# Motor_Controllers.net
KiCad netlist of a schematic drawn in Altium Designer
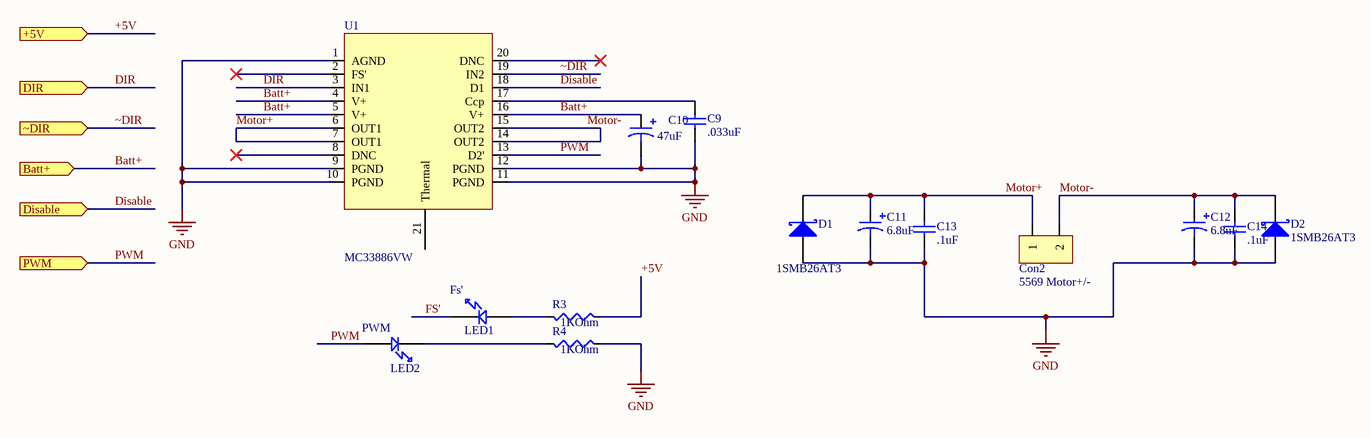
[diagram p0: Motor Controllers.SchDoc]

(export (version "E")
  (design (tool "Eeschema 10.0.6"))
  (components
    (comp (ref "C9")
      (value ".033uF")
      (footprint "PassiveComponents:0805 (2012) Capacitor")
      (description "Capacitor")
      (libsource (lib "PassiveComponents") (part "Capacitor (non-polarized)"))
    )
    (comp (ref "C10")
      (value "47uF")
      (footprint "PassiveComponents:Radial_6.3mmDia_SM_D")
      (description "Capacitor (polarized)")
      (libsource (lib "PassiveComponents") (part "Capacitor (polarized)"))
    )
    (comp (ref "C11")
      (value "6.8uF")
      (footprint "PassiveComponents:Radial_8mmDia_SM_E")
      (description "Capacitor (polarized)")
      (libsource (lib "PassiveComponents") (part "Capacitor (polarized)"))
    )
    (comp (ref "C12")
      (value "6.8uF")
      (footprint "PassiveComponents:Radial_8mmDia_SM_E")
      (description "Capacitor (polarized)")
      (libsource (lib "PassiveComponents") (part "Capacitor (polarized)"))
    )
    (comp (ref "C13")
      (value ".1uF")
      (footprint "PassiveComponents:0805 (2012) Capacitor")
      (description "Capacitor")
      (libsource (lib "PassiveComponents") (part "Capacitor (non-polarized)"))
    )
    (comp (ref "C14")
      (value ".1uF")
      (footprint "PassiveComponents:0805 (2012) Capacitor")
      (description "Capacitor")
      (libsource (lib "PassiveComponents") (part "Capacitor (non-polarized)"))
    )
    (comp (ref "Con2")
      (value "5569 Motor+/-")
      (footprint "Molex:5569 Mini-Fit Jr 2-Pos Right Angle w/ PCB Mounting Flange")
      (libsource (lib "Molex") (part "5569 Mini-Fit Jr 2-Pos Right Angle"))
    )
    (comp (ref "D1")
      (value "1SMB26AT3")
      (footprint "SMB")
      (description "Schottky Diode")
      (fields (field (name "PUBLISHER") "Altium Limited"))
      (libsource (lib "Miscellaneous Devices") (part "D Schottky"))
    )
    (comp (ref "D2")
      (value "1SMB26AT3")
      (footprint "SMB")
      (description "Schottky Diode")
      (fields (field (name "PUBLISHER") "Altium Limited"))
      (libsource (lib "Miscellaneous Devices") (part "D Schottky"))
    )
    (comp (ref "LED1")
      (value "Fs'")
      (footprint "LEDs:LED 0805")
      (description "Standard LED")
      (libsource (lib "PassiveComponents") (part "LED"))
    )
    (comp (ref "LED2")
      (value "PWM")
      (footprint "LEDs:LED 0805")
      (description "Standard LED")
      (libsource (lib "PassiveComponents") (part "LED"))
    )
    (comp (ref "R3")
      (value "1KOhm")
      (footprint "PassiveComponents:R 0805 (2012) RESISTOR")
      (description "Resistor")
      (libsource (lib "PassiveComponents") (part "Resistor"))
    )
    (comp (ref "R4")
      (value "1KOhm")
      (footprint "PassiveComponents:R 0805 (2012) RESISTOR")
      (description "Resistor")
      (libsource (lib "PassiveComponents") (part "Resistor"))
    )
    (comp (ref "U1")
      (value "MC33886VW")
      (footprint "SOP127P1420X340_HS-20N")
      (description "Motor Controller")
      (libsource (lib "MC33886VW") (part "MC33886VW"))
    )
  )
  (nets
    (net (code "1") (name "/+5V") (class "Default")
      (node (ref "R3") (pin "2") (pinfunction "2_2") (pintype "passive"))
    )
    (net (code "2") (name "/Batt+") (class "Default")
      (node (ref "C10") (pin "P") (pinfunction "1_P") (pintype "passive"))
      (node (ref "U1") (pin "16") (pinfunction "V+_16") (pintype "passive"))
      (node (ref "U1") (pin "4") (pinfunction "V+_4") (pintype "passive"))
      (node (ref "U1") (pin "5") (pinfunction "V+_5") (pintype "passive"))
    )
    (net (code "3") (name "/DIR") (class "Default")
      (node (ref "U1") (pin "3") (pinfunction "IN1_3") (pintype "passive"))
    )
    (net (code "4") (name "/Disable") (class "Default")
      (node (ref "U1") (pin "18") (pinfunction "D1_18") (pintype "passive"))
    )
    (net (code "5") (name "/FS'") (class "Default")
      (node (ref "LED1") (pin "1") (pinfunction "1_1") (pintype "passive"))
    )
    (net (code "6") (name "/Motor+") (class "Default")
      (node (ref "C11") (pin "P") (pinfunction "1_P") (pintype "passive"))
      (node (ref "C13") (pin "2") (pinfunction "2_2") (pintype "passive"))
      (node (ref "Con2") (pin "1") (pinfunction "1_1") (pintype "passive"))
      (node (ref "D1") (pin "2") (pinfunction "K_2") (pintype "passive"))
      (node (ref "U1") (pin "6") (pinfunction "OUT1_6") (pintype "passive"))
      (node (ref "U1") (pin "7") (pinfunction "OUT1_7") (pintype "passive"))
    )
    (net (code "7") (name "/Motor-") (class "Default")
      (node (ref "C12") (pin "P") (pinfunction "1_P") (pintype "passive"))
      (node (ref "C14") (pin "2") (pinfunction "2_2") (pintype "passive"))
      (node (ref "Con2") (pin "2") (pinfunction "2_2") (pintype "passive"))
      (node (ref "D2") (pin "2") (pinfunction "K_2") (pintype "passive"))
      (node (ref "U1") (pin "14") (pinfunction "OUT2_14") (pintype "passive"))
      (node (ref "U1") (pin "15") (pinfunction "OUT2_15") (pintype "passive"))
    )
    (net (code "8") (name "/PWM") (class "Default")
      (node (ref "LED2") (pin "2") (pinfunction "2_2") (pintype "passive"))
      (node (ref "U1") (pin "13") (pinfunction "D2'_13") (pintype "passive"))
    )
    (net (code "9") (name "/~DIR") (class "Default")
      (node (ref "U1") (pin "19") (pinfunction "IN2_19") (pintype "passive"))
    )
    (net (code "10") (name "GND") (class "Default")
      (node (ref "C10") (pin "N") (pinfunction "2_N") (pintype "passive"))
      (node (ref "C11") (pin "N") (pinfunction "2_N") (pintype "passive"))
      (node (ref "C12") (pin "N") (pinfunction "2_N") (pintype "passive"))
      (node (ref "C13") (pin "1") (pinfunction "1_1") (pintype "passive"))
      (node (ref "C14") (pin "1") (pinfunction "1_1") (pintype "passive"))
      (node (ref "C9") (pin "1") (pinfunction "1_1") (pintype "passive"))
      (node (ref "D1") (pin "1") (pinfunction "A_1") (pintype "passive"))
      (node (ref "D2") (pin "1") (pinfunction "A_1") (pintype "passive"))
      (node (ref "R4") (pin "2") (pinfunction "2_2") (pintype "passive"))
      (node (ref "U1") (pin "1") (pinfunction "AGND_1") (pintype "passive"))
      (node (ref "U1") (pin "10") (pinfunction "PGND_10") (pintype "passive"))
      (node (ref "U1") (pin "11") (pinfunction "PGND_11") (pintype "passive"))
      (node (ref "U1") (pin "12") (pinfunction "PGND_12") (pintype "passive"))
      (node (ref "U1") (pin "9") (pinfunction "PGND_9") (pintype "passive"))
    )
    (net (code "11") (name "Net-(LED1-Pad2)") (class "Default")
      (node (ref "LED1") (pin "2") (pinfunction "2_2") (pintype "passive"))
      (node (ref "R3") (pin "1") (pinfunction "1_1") (pintype "passive"))
    )
    (net (code "12") (name "Net-(LED2-Pad1)") (class "Default")
      (node (ref "LED2") (pin "1") (pinfunction "1_1") (pintype "passive"))
      (node (ref "R4") (pin "1") (pinfunction "1_1") (pintype "passive"))
    )
    (net (code "13") (name "Net-(U1-Ccp)") (class "Default")
      (node (ref "C9") (pin "2") (pinfunction "2_2") (pintype "passive"))
      (node (ref "U1") (pin "17") (pinfunction "Ccp_17") (pintype "passive"))
    )
    (net (code "14") (name "unconnected-(U1-DNC-Pad8)") (class "Default")
      (node (ref "U1") (pin "8") (pinfunction "DNC_8") (pintype "passive+no_connect"))
    )
    (net (code "15") (name "unconnected-(U1-DNC-Pad20)") (class "Default")
      (node (ref "U1") (pin "20") (pinfunction "DNC_20") (pintype "passive+no_connect"))
    )
    (net (code "16") (name "unconnected-(U1-FS'-Pad2)") (class "Default")
      (node (ref "U1") (pin "2") (pinfunction "FS'_2") (pintype "passive+no_connect"))
    )
    (net (code "17") (name "unconnected-(U1-Thermal-Pad21)") (class "Default")
      (node (ref "U1") (pin "21") (pinfunction "Thermal_21") (pintype "passive"))
    )
  )
)
